# 1_P1.net
KiCad netlist of a schematic drawn in Altium Designer
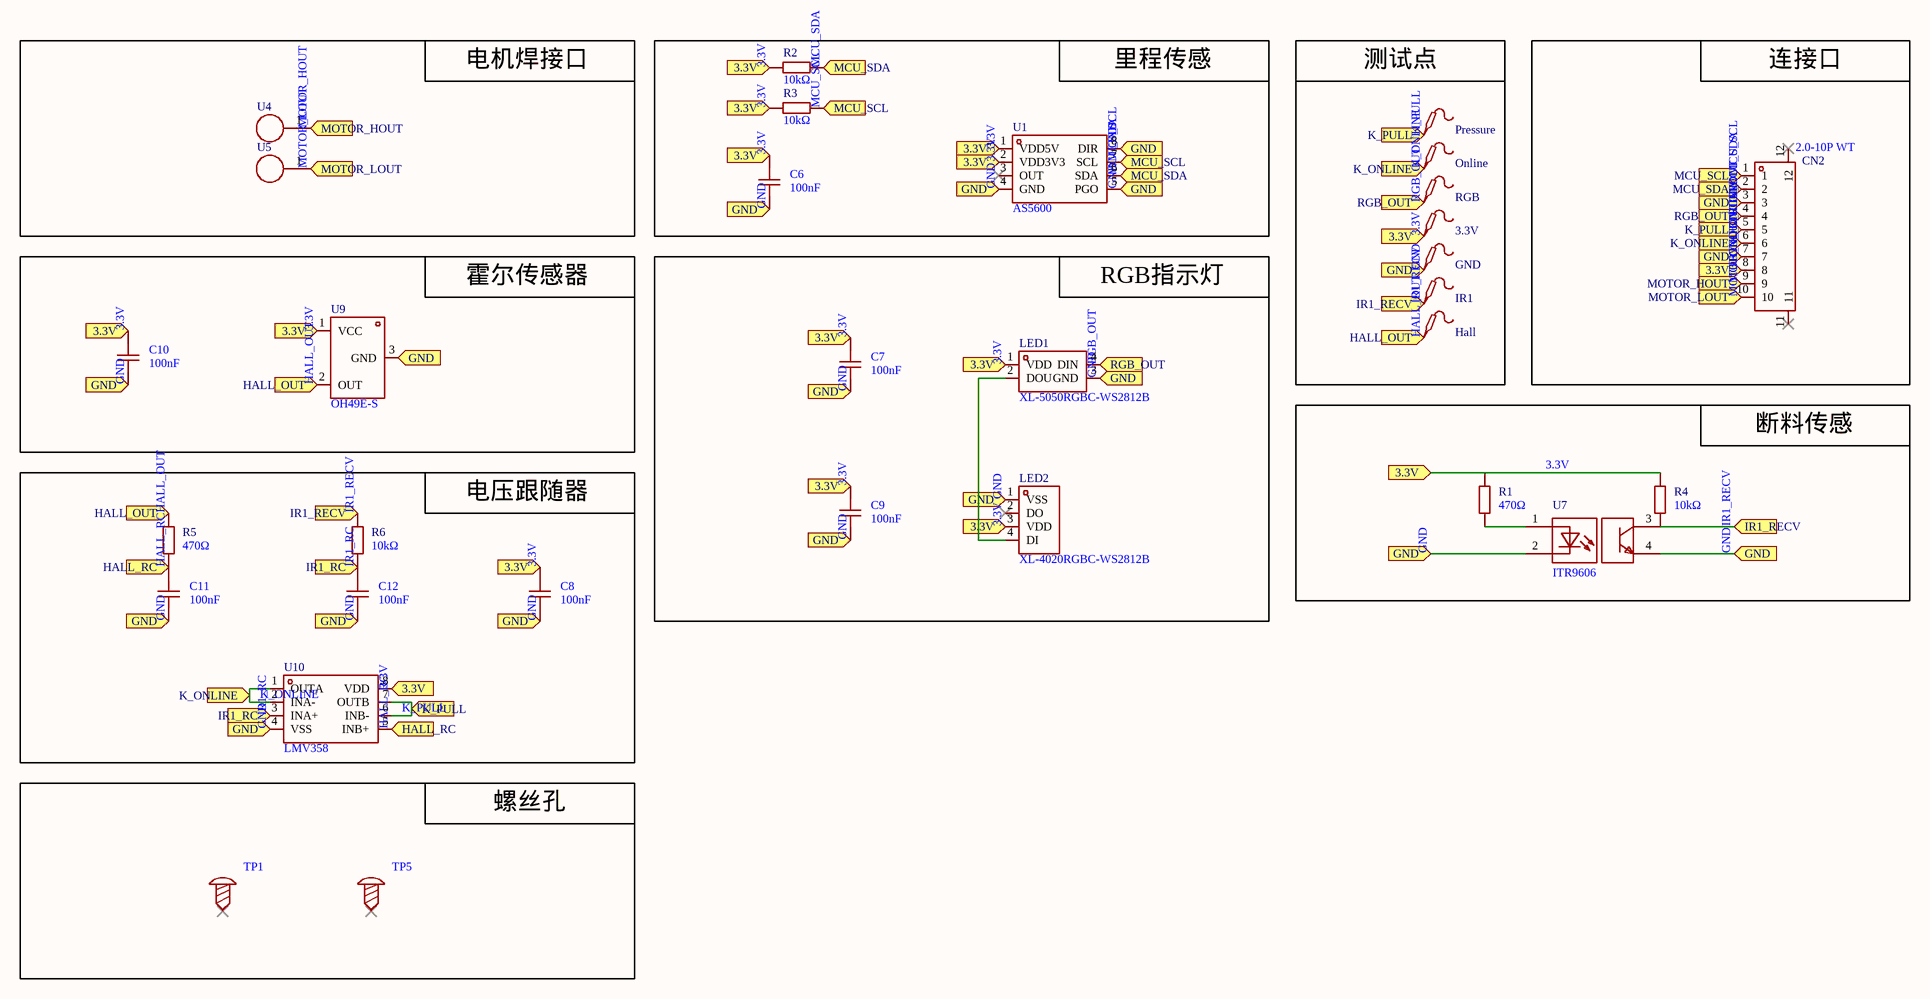
[diagram p0: 1_P1.schdoc]

(export (version "E")
  (design (tool "Eeschema 10.0.6"))
  (components
    (comp (ref "3.3V")
      (value "~")
      (footprint "Test-Point-0.5mm")
      (libsource (lib "altium-import") (part "root_0_Test-Point_"))
    )
    (comp (ref "C6")
      (value "100nF")
      (footprint "C0603")
      (fields
        (field (name "MANUFACTURER") "YAGEO(国巨)")
        (field (name "MANUFACTURER PART") "CC0603KRX7R9BB104")
        (field (name "ALTIUM_VALUE") "100nF")
        (field (name "TOLERANCE") "±10%")
      )
      (libsource (lib "altium-import") (part "root_1_CC0603KRX7R9BB104_"))
    )
    (comp (ref "C7")
      (value "100nF")
      (footprint "C0603")
      (fields
        (field (name "MANUFACTURER") "YAGEO(国巨)")
        (field (name "MANUFACTURER PART") "CC0603KRX7R9BB104")
        (field (name "ALTIUM_VALUE") "100nF")
        (field (name "TOLERANCE") "±10%")
      )
      (libsource (lib "altium-import") (part "root_1_CC0603KRX7R9BB104_"))
    )
    (comp (ref "C8")
      (value "100nF")
      (footprint "C0603")
      (fields
        (field (name "MANUFACTURER") "YAGEO(国巨)")
        (field (name "MANUFACTURER PART") "CC0603KRX7R9BB104")
        (field (name "ALTIUM_VALUE") "100nF")
        (field (name "TOLERANCE") "±10%")
      )
      (libsource (lib "altium-import") (part "root_1_CC0603KRX7R9BB104_"))
    )
    (comp (ref "C9")
      (value "100nF")
      (footprint "C0603")
      (fields
        (field (name "MANUFACTURER") "YAGEO(国巨)")
        (field (name "MANUFACTURER PART") "CC0603KRX7R9BB104")
        (field (name "ALTIUM_VALUE") "100nF")
        (field (name "TOLERANCE") "±10%")
      )
      (libsource (lib "altium-import") (part "root_1_CC0603KRX7R9BB104_"))
    )
    (comp (ref "C10")
      (value "100nF")
      (footprint "C0603")
      (fields
        (field (name "MANUFACTURER") "YAGEO(国巨)")
        (field (name "MANUFACTURER PART") "CC0603KRX7R9BB104")
        (field (name "ALTIUM_VALUE") "100nF")
        (field (name "TOLERANCE") "±10%")
      )
      (libsource (lib "altium-import") (part "root_1_CC0603KRX7R9BB104_"))
    )
    (comp (ref "C11")
      (value "100nF")
      (footprint "C0603")
      (fields
        (field (name "MANUFACTURER") "YAGEO(国巨)")
        (field (name "MANUFACTURER PART") "CC0603KRX7R9BB104")
        (field (name "ALTIUM_VALUE") "100nF")
        (field (name "TOLERANCE") "±10%")
      )
      (libsource (lib "altium-import") (part "root_1_CC0603KRX7R9BB104_"))
    )
    (comp (ref "C12")
      (value "100nF")
      (footprint "C0603")
      (fields
        (field (name "MANUFACTURER") "YAGEO(国巨)")
        (field (name "MANUFACTURER PART") "CC0603KRX7R9BB104")
        (field (name "ALTIUM_VALUE") "100nF")
        (field (name "TOLERANCE") "±10%")
      )
      (libsource (lib "altium-import") (part "root_1_CC0603KRX7R9BB104_"))
    )
    (comp (ref "CN2")
      (value "2.0-10P WT")
      (footprint "CONN-SMD_10P-P2.00_2.0-10P-WT")
      (fields (field (name "MANUFACTURER") "SHOU HAN(首韩)"))
      (libsource (lib "altium-import") (part "root_0_2.0-10P WT_"))
    )
    (comp (ref "GND")
      (value "~")
      (footprint "Test-Point-0.5mm")
      (libsource (lib "altium-import") (part "root_0_Test-Point_"))
    )
    (comp (ref "Hall")
      (value "~")
      (footprint "Test-Point-0.5mm")
      (libsource (lib "altium-import") (part "root_0_Test-Point_"))
    )
    (comp (ref "IR1")
      (value "~")
      (footprint "Test-Point-0.5mm")
      (libsource (lib "altium-import") (part "root_0_Test-Point_"))
    )
    (comp (ref "LED1")
      (value "XL-5050RGBC-WS2812B")
      (footprint "LED-SMD_4P-L5.0-W5.0-BL_XL-5050RGBC")
      (fields (field (name "MANUFACTURER") "XINGLIGHT(成兴光)"))
      (libsource (lib "altium-import") (part "root_0_XL-5050RGBC-WS2812B_"))
    )
    (comp (ref "LED2")
      (value "XL-4020RGBC-WS2812B")
      (footprint "LED-SMD_4P-L4.0-W1.7_XL-4020RGBC-WS2812B")
      (fields (field (name "MANUFACTURER") "XINGLIGHT(成兴光)"))
      (libsource (lib "altium-import") (part "root_0_XL-4020RGBC-WS2812B_"))
    )
    (comp (ref "Online")
      (value "~")
      (footprint "Test-Point-0.5mm")
      (libsource (lib "altium-import") (part "root_0_Test-Point_"))
    )
    (comp (ref "Pressure")
      (value "~")
      (footprint "Test-Point-0.5mm")
      (libsource (lib "altium-import") (part "root_0_Test-Point_"))
    )
    (comp (ref "R1")
      (value "470Ω")
      (footprint "R0603")
      (fields
        (field (name "MANUFACTURER") "UNI-ROYAL(厚声)")
        (field (name "MANUFACTURER PART") "0603WAF4700T5E")
        (field (name "TOLERANCE") "±1%")
      )
      (libsource (lib "altium-import") (part "root_3_0603WAF4700T5E_"))
    )
    (comp (ref "R2")
      (value "10kΩ")
      (footprint "R0603")
      (fields
        (field (name "MANUFACTURER") "UNI-ROYAL(厚声)")
        (field (name "MANUFACTURER PART") "0603WAF1002T5E")
        (field (name "TOLERANCE") "±1%")
      )
      (libsource (lib "altium-import") (part "root_0_0603WAF1002T5E_"))
    )
    (comp (ref "R3")
      (value "10kΩ")
      (footprint "R0603")
      (fields
        (field (name "MANUFACTURER") "UNI-ROYAL(厚声)")
        (field (name "MANUFACTURER PART") "0603WAF1002T5E")
        (field (name "TOLERANCE") "±1%")
      )
      (libsource (lib "altium-import") (part "root_0_0603WAF1002T5E_"))
    )
    (comp (ref "R4")
      (value "10kΩ")
      (footprint "R0603")
      (fields
        (field (name "MANUFACTURER") "UNI-ROYAL(厚声)")
        (field (name "MANUFACTURER PART") "0603WAF1002T5E")
        (field (name "TOLERANCE") "±1%")
      )
      (libsource (lib "altium-import") (part "root_3_0603WAF1002T5E_"))
    )
    (comp (ref "R5")
      (value "470Ω")
      (footprint "R0603")
      (fields
        (field (name "MANUFACTURER") "UNI-ROYAL(厚声)")
        (field (name "MANUFACTURER PART") "0603WAF4700T5E")
        (field (name "TOLERANCE") "±1%")
      )
      (libsource (lib "altium-import") (part "root_3_0603WAF4700T5E_"))
    )
    (comp (ref "R6")
      (value "10kΩ")
      (footprint "R0603")
      (fields
        (field (name "MANUFACTURER") "UNI-ROYAL(厚声)")
        (field (name "MANUFACTURER PART") "0603WAF1002T5E")
        (field (name "TOLERANCE") "±1%")
      )
      (libsource (lib "altium-import") (part "root_1_0603WAF1002T5E_"))
    )
    (comp (ref "RGB")
      (value "~")
      (footprint "Test-Point-0.5mm")
      (libsource (lib "altium-import") (part "root_0_Test-Point_"))
    )
    (comp (ref "TP1") (value "~") (footprint "M2螺丝") (libsource (lib "altium-import") (part "root_0_M2螺丝_")))
    (comp (ref "TP5") (value "~") (footprint "M2螺丝") (libsource (lib "altium-import") (part "root_0_M2螺丝_")))
    (comp (ref "U1")
      (value "AS5600")
      (footprint "SOIC-8_L4.9-W3.9-P1.27-LS6.0-BL")
      (libsource (lib "altium-import") (part "root_0_AS5600_"))
    )
    (comp (ref "U4")
      (value "1625854-2")
      (footprint "TEST-RING")
      (fields (field (name "MANUFACTURER") "TE Connectivity(泰科电子)"))
      (libsource (lib "altium-import") (part "root_1_1625854-2_"))
    )
    (comp (ref "U5")
      (value "1625854-2")
      (footprint "TEST-RING")
      (fields (field (name "MANUFACTURER") "TE Connectivity(泰科电子)"))
      (libsource (lib "altium-import") (part "root_1_1625854-2_"))
    )
    (comp (ref "U7")
      (value "ITR9606")
      (footprint "OPTO-TH_4P_ITR9606")
      (fields (field (name "MANUFACTURER") "EVERLIGHT(亿光)"))
      (libsource (lib "altium-import") (part "root_0_ITR9606_"))
    )
    (comp (ref "U9")
      (value "OH49E-S")
      (footprint "SOT-23-3_L2.9-W1.6-P1.90-LS2.8-BR")
      (fields (field (name "MANUFACTURER") "南京欧卓"))
      (libsource (lib "altium-import") (part "root_3_OH49E-S_"))
    )
    (comp (ref "U10")
      (value "LMV358")
      (footprint "SOP-8_L4.9-W3.9-P1.27-LS6.0-BL")
      (fields (field (name "MANUFACTURER") "TECH PUBLIC(台舟)"))
      (libsource (lib "altium-import") (part "root_0_LMV358_"))
    )
  )
  (nets
    (net (code "1") (name "/3.3V") (class "Default")
      (node (ref "3.3V") (pin "1") (pinfunction "1_1") (pintype "passive"))
      (node (ref "C10") (pin "2") (pinfunction "2_2") (pintype "passive"))
      (node (ref "C6") (pin "2") (pinfunction "2_2") (pintype "passive"))
      (node (ref "C7") (pin "2") (pinfunction "2_2") (pintype "passive"))
      (node (ref "C8") (pin "2") (pinfunction "2_2") (pintype "passive"))
      (node (ref "C9") (pin "2") (pinfunction "2_2") (pintype "passive"))
      (node (ref "CN2") (pin "8") (pinfunction "8_8") (pintype "passive"))
      (node (ref "LED1") (pin "1") (pinfunction "VDD_1") (pintype "passive"))
      (node (ref "LED2") (pin "3") (pinfunction "VDD_3") (pintype "passive"))
      (node (ref "R1") (pin "1") (pinfunction "1_1") (pintype "passive"))
      (node (ref "R2") (pin "1") (pinfunction "1_1") (pintype "passive"))
      (node (ref "R3") (pin "1") (pinfunction "1_1") (pintype "passive"))
      (node (ref "R4") (pin "1") (pinfunction "1_1") (pintype "passive"))
      (node (ref "U1") (pin "1") (pinfunction "VDD5V_1") (pintype "passive"))
      (node (ref "U1") (pin "2") (pinfunction "VDD3V3_2") (pintype "passive"))
      (node (ref "U10") (pin "8") (pinfunction "VDD_8") (pintype "passive"))
      (node (ref "U9") (pin "1") (pinfunction "VCC_1") (pintype "passive"))
    )
    (net (code "2") (name "/GND") (class "Default")
      (node (ref "C10") (pin "1") (pinfunction "1_1") (pintype "passive"))
      (node (ref "C11") (pin "1") (pinfunction "1_1") (pintype "passive"))
      (node (ref "C12") (pin "1") (pinfunction "1_1") (pintype "passive"))
      (node (ref "C6") (pin "1") (pinfunction "1_1") (pintype "passive"))
      (node (ref "C7") (pin "1") (pinfunction "1_1") (pintype "passive"))
      (node (ref "C8") (pin "1") (pinfunction "1_1") (pintype "passive"))
      (node (ref "C9") (pin "1") (pinfunction "1_1") (pintype "passive"))
      (node (ref "CN2") (pin "3") (pinfunction "3_3") (pintype "passive"))
      (node (ref "CN2") (pin "7") (pinfunction "7_7") (pintype "passive"))
      (node (ref "GND") (pin "1") (pinfunction "1_1") (pintype "passive"))
      (node (ref "LED1") (pin "3") (pinfunction "GND_3") (pintype "passive"))
      (node (ref "LED2") (pin "1") (pinfunction "VSS_1") (pintype "passive"))
      (node (ref "U1") (pin "4") (pinfunction "GND_4") (pintype "passive"))
      (node (ref "U1") (pin "5") (pinfunction "PGO_5") (pintype "passive"))
      (node (ref "U1") (pin "8") (pinfunction "DIR_8") (pintype "passive"))
      (node (ref "U10") (pin "4") (pinfunction "VSS_4") (pintype "passive"))
      (node (ref "U7") (pin "2") (pinfunction "2_2") (pintype "passive"))
      (node (ref "U7") (pin "4") (pinfunction "4_4") (pintype "passive"))
      (node (ref "U9") (pin "3") (pinfunction "GND_3") (pintype "passive"))
    )
    (net (code "3") (name "/HALL_OUT") (class "Default")
      (node (ref "Hall") (pin "1") (pinfunction "1_1") (pintype "passive"))
      (node (ref "R5") (pin "1") (pinfunction "1_1") (pintype "passive"))
      (node (ref "U9") (pin "2") (pinfunction "OUT_2") (pintype "passive"))
    )
    (net (code "4") (name "/HALL_RC") (class "Default")
      (node (ref "C11") (pin "2") (pinfunction "2_2") (pintype "passive"))
      (node (ref "R5") (pin "2") (pinfunction "2_2") (pintype "passive"))
      (node (ref "U10") (pin "5") (pinfunction "INB+_5") (pintype "passive"))
    )
    (net (code "5") (name "/IR1_RC") (class "Default")
      (node (ref "C12") (pin "2") (pinfunction "2_2") (pintype "passive"))
      (node (ref "R6") (pin "1") (pinfunction "1_1") (pintype "passive"))
      (node (ref "U10") (pin "3") (pinfunction "INA+_3") (pintype "passive"))
    )
    (net (code "6") (name "/IR1_RECV") (class "Default")
      (node (ref "IR1") (pin "1") (pinfunction "1_1") (pintype "passive"))
      (node (ref "R4") (pin "2") (pinfunction "2_2") (pintype "passive"))
      (node (ref "R6") (pin "2") (pinfunction "2_2") (pintype "passive"))
      (node (ref "U7") (pin "3") (pinfunction "3_3") (pintype "passive"))
    )
    (net (code "7") (name "/K_ONLINE") (class "Default")
      (node (ref "CN2") (pin "6") (pinfunction "6_6") (pintype "passive"))
      (node (ref "Online") (pin "1") (pinfunction "1_1") (pintype "passive"))
      (node (ref "U10") (pin "1") (pinfunction "OUTA_1") (pintype "passive"))
      (node (ref "U10") (pin "2") (pinfunction "INA-_2") (pintype "passive"))
    )
    (net (code "8") (name "/K_PULL") (class "Default")
      (node (ref "CN2") (pin "5") (pinfunction "5_5") (pintype "passive"))
      (node (ref "Pressure") (pin "1") (pinfunction "1_1") (pintype "passive"))
      (node (ref "U10") (pin "6") (pinfunction "INB-_6") (pintype "passive"))
      (node (ref "U10") (pin "7") (pinfunction "OUTB_7") (pintype "passive"))
    )
    (net (code "9") (name "/MCU_SCL") (class "Default")
      (node (ref "CN2") (pin "1") (pinfunction "1_1") (pintype "passive"))
      (node (ref "R3") (pin "2") (pinfunction "2_2") (pintype "passive"))
      (node (ref "U1") (pin "7") (pinfunction "SCL_7") (pintype "passive"))
    )
    (net (code "10") (name "/MCU_SDA") (class "Default")
      (node (ref "CN2") (pin "2") (pinfunction "2_2") (pintype "passive"))
      (node (ref "R2") (pin "2") (pinfunction "2_2") (pintype "passive"))
      (node (ref "U1") (pin "6") (pinfunction "SDA_6") (pintype "passive"))
    )
    (net (code "11") (name "/MOTOR_HOUT") (class "Default")
      (node (ref "CN2") (pin "9") (pinfunction "9_9") (pintype "passive"))
      (node (ref "U4") (pin "1") (pinfunction "1_1") (pintype "passive"))
    )
    (net (code "12") (name "/MOTOR_LOUT") (class "Default")
      (node (ref "CN2") (pin "10") (pinfunction "10_10") (pintype "passive"))
      (node (ref "U5") (pin "1") (pinfunction "1_1") (pintype "passive"))
    )
    (net (code "13") (name "/RGB_OUT") (class "Default")
      (node (ref "CN2") (pin "4") (pinfunction "4_4") (pintype "passive"))
      (node (ref "LED1") (pin "4") (pinfunction "DIN_4") (pintype "passive"))
      (node (ref "RGB") (pin "1") (pinfunction "1_1") (pintype "passive"))
    )
    (net (code "14") (name "Net-(LED1-DOU)") (class "Default")
      (node (ref "LED1") (pin "2") (pinfunction "DOU_2") (pintype "passive"))
      (node (ref "LED2") (pin "4") (pinfunction "DI_4") (pintype "passive"))
    )
    (net (code "15") (name "Net-(R1-Pad2)") (class "Default")
      (node (ref "R1") (pin "2") (pinfunction "2_2") (pintype "passive"))
      (node (ref "U7") (pin "1") (pinfunction "1_1") (pintype "passive"))
    )
    (net (code "16") (name "unconnected-(CN2-Pad11)") (class "Default")
      (node (ref "CN2") (pin "11") (pinfunction "11_11") (pintype "passive+no_connect"))
    )
    (net (code "17") (name "unconnected-(CN2-Pad12)") (class "Default")
      (node (ref "CN2") (pin "12") (pinfunction "12_12") (pintype "passive+no_connect"))
    )
    (net (code "18") (name "unconnected-(LED2-DO-Pad2)") (class "Default")
      (node (ref "LED2") (pin "2") (pinfunction "DO_2") (pintype "passive+no_connect"))
    )
    (net (code "19") (name "unconnected-(TP1-Pad1)") (class "Default")
      (node (ref "TP1") (pin "1") (pinfunction "1_1") (pintype "passive+no_connect"))
    )
    (net (code "20") (name "unconnected-(TP5-Pad1)") (class "Default")
      (node (ref "TP5") (pin "1") (pinfunction "1_1") (pintype "passive+no_connect"))
    )
    (net (code "21") (name "unconnected-(U1-OUT-Pad3)") (class "Default")
      (node (ref "U1") (pin "3") (pinfunction "OUT_3") (pintype "passive+no_connect"))
    )
  )
)
